# H0FR1.net
KiCad netlist of a schematic drawn in EAGLE
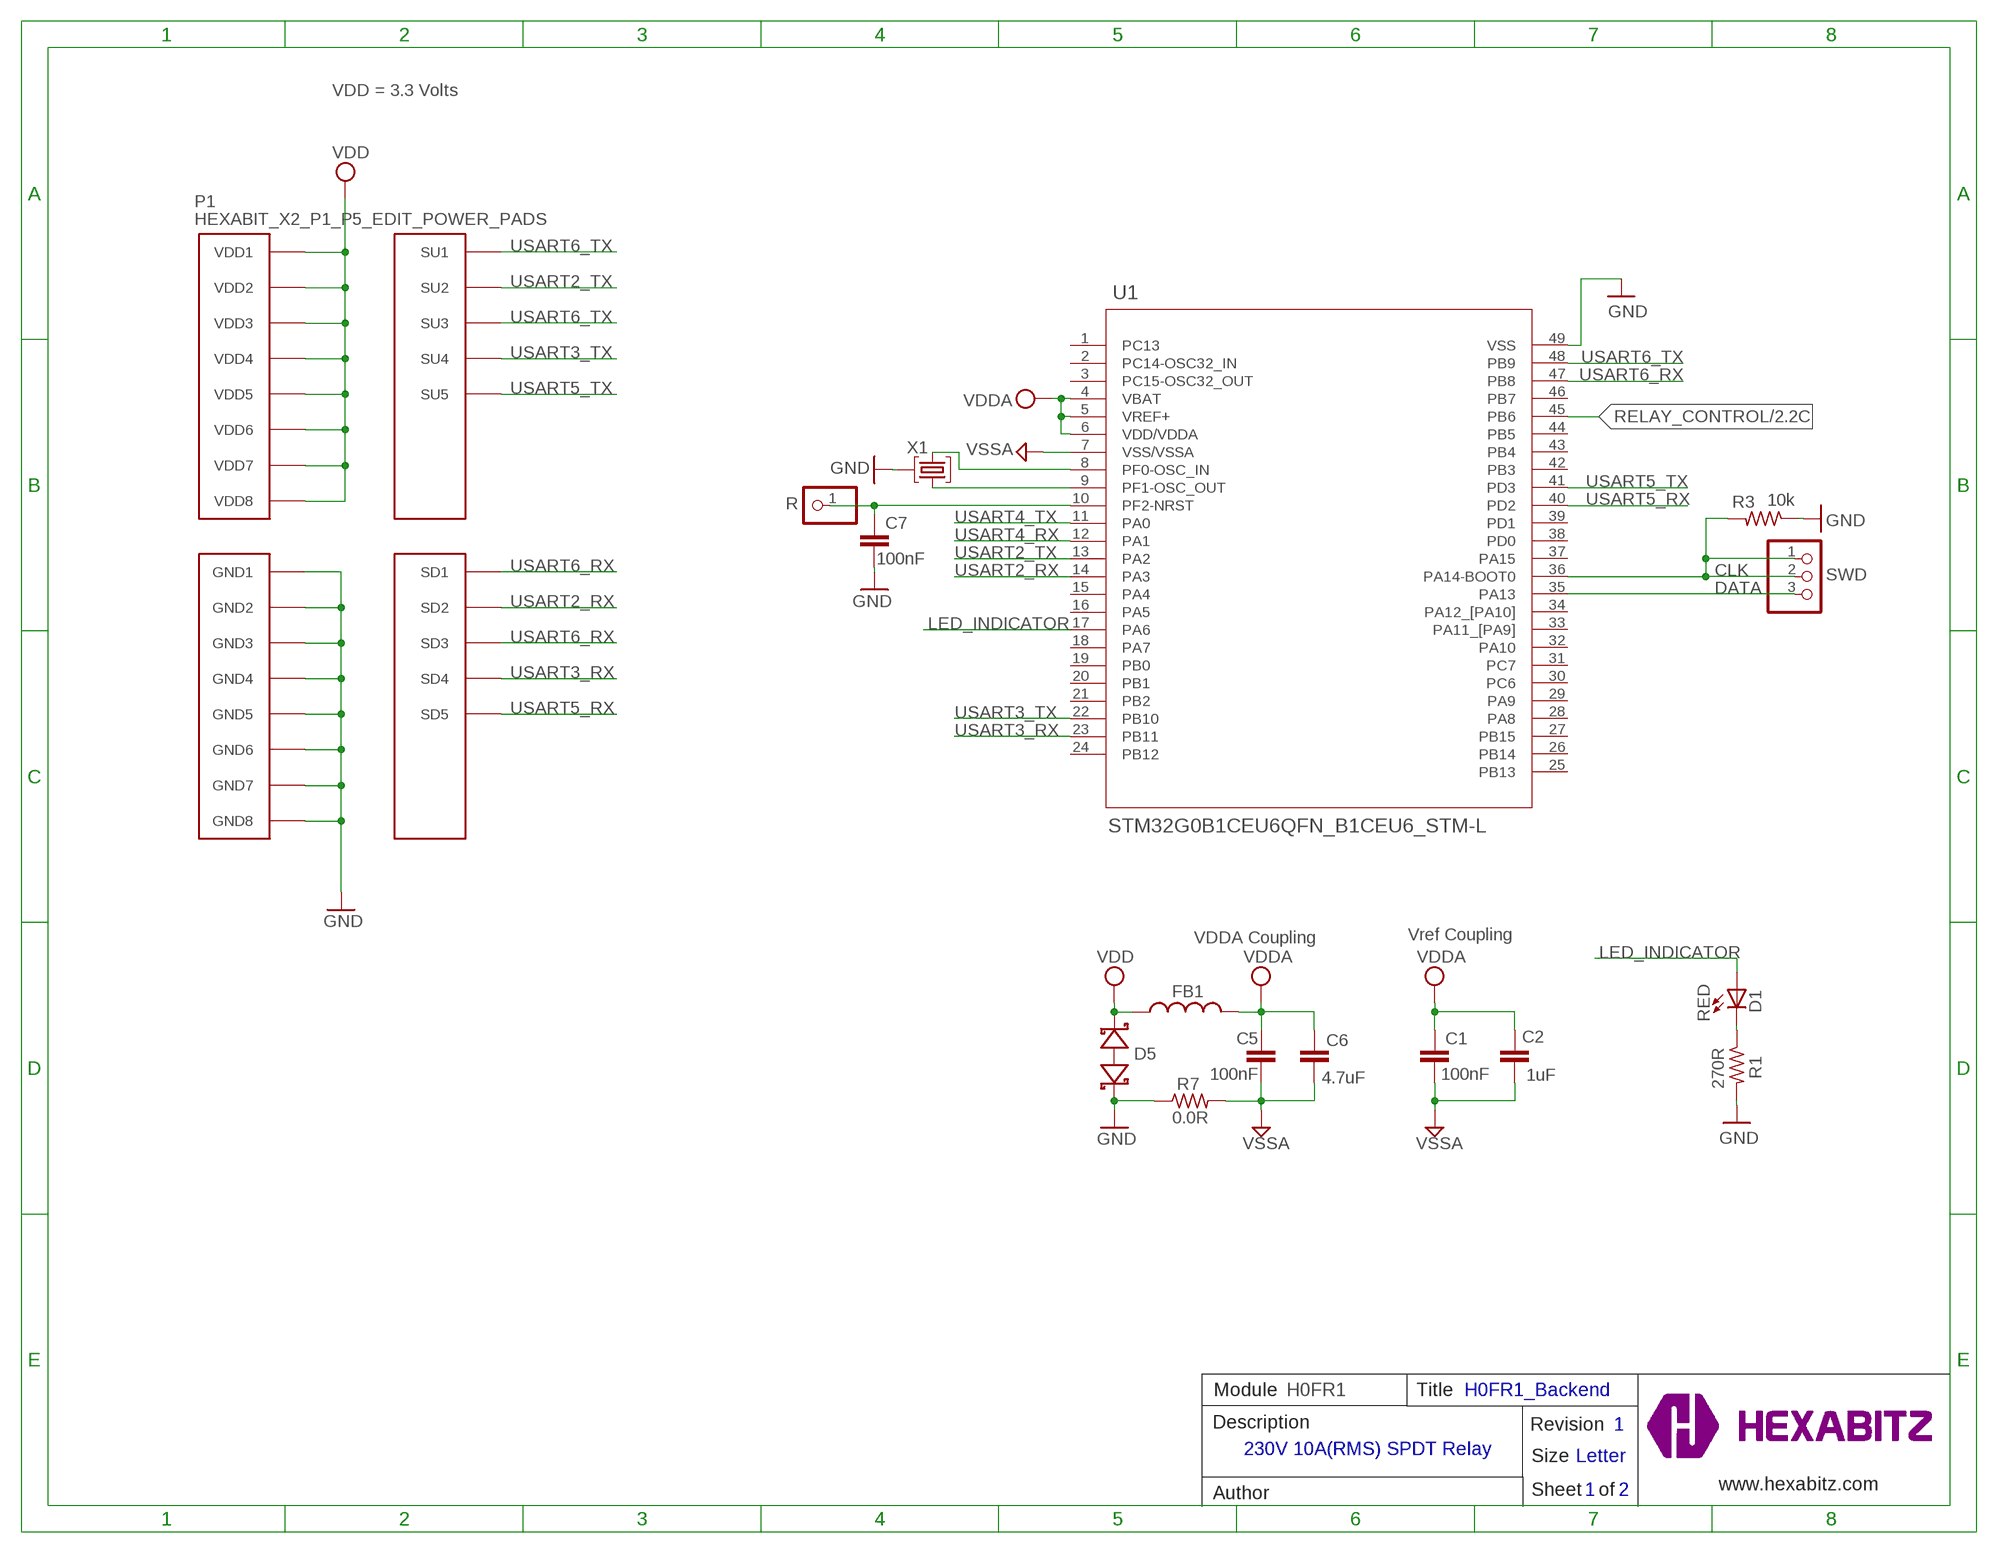
[diagram p0: schematic, sheet 1]
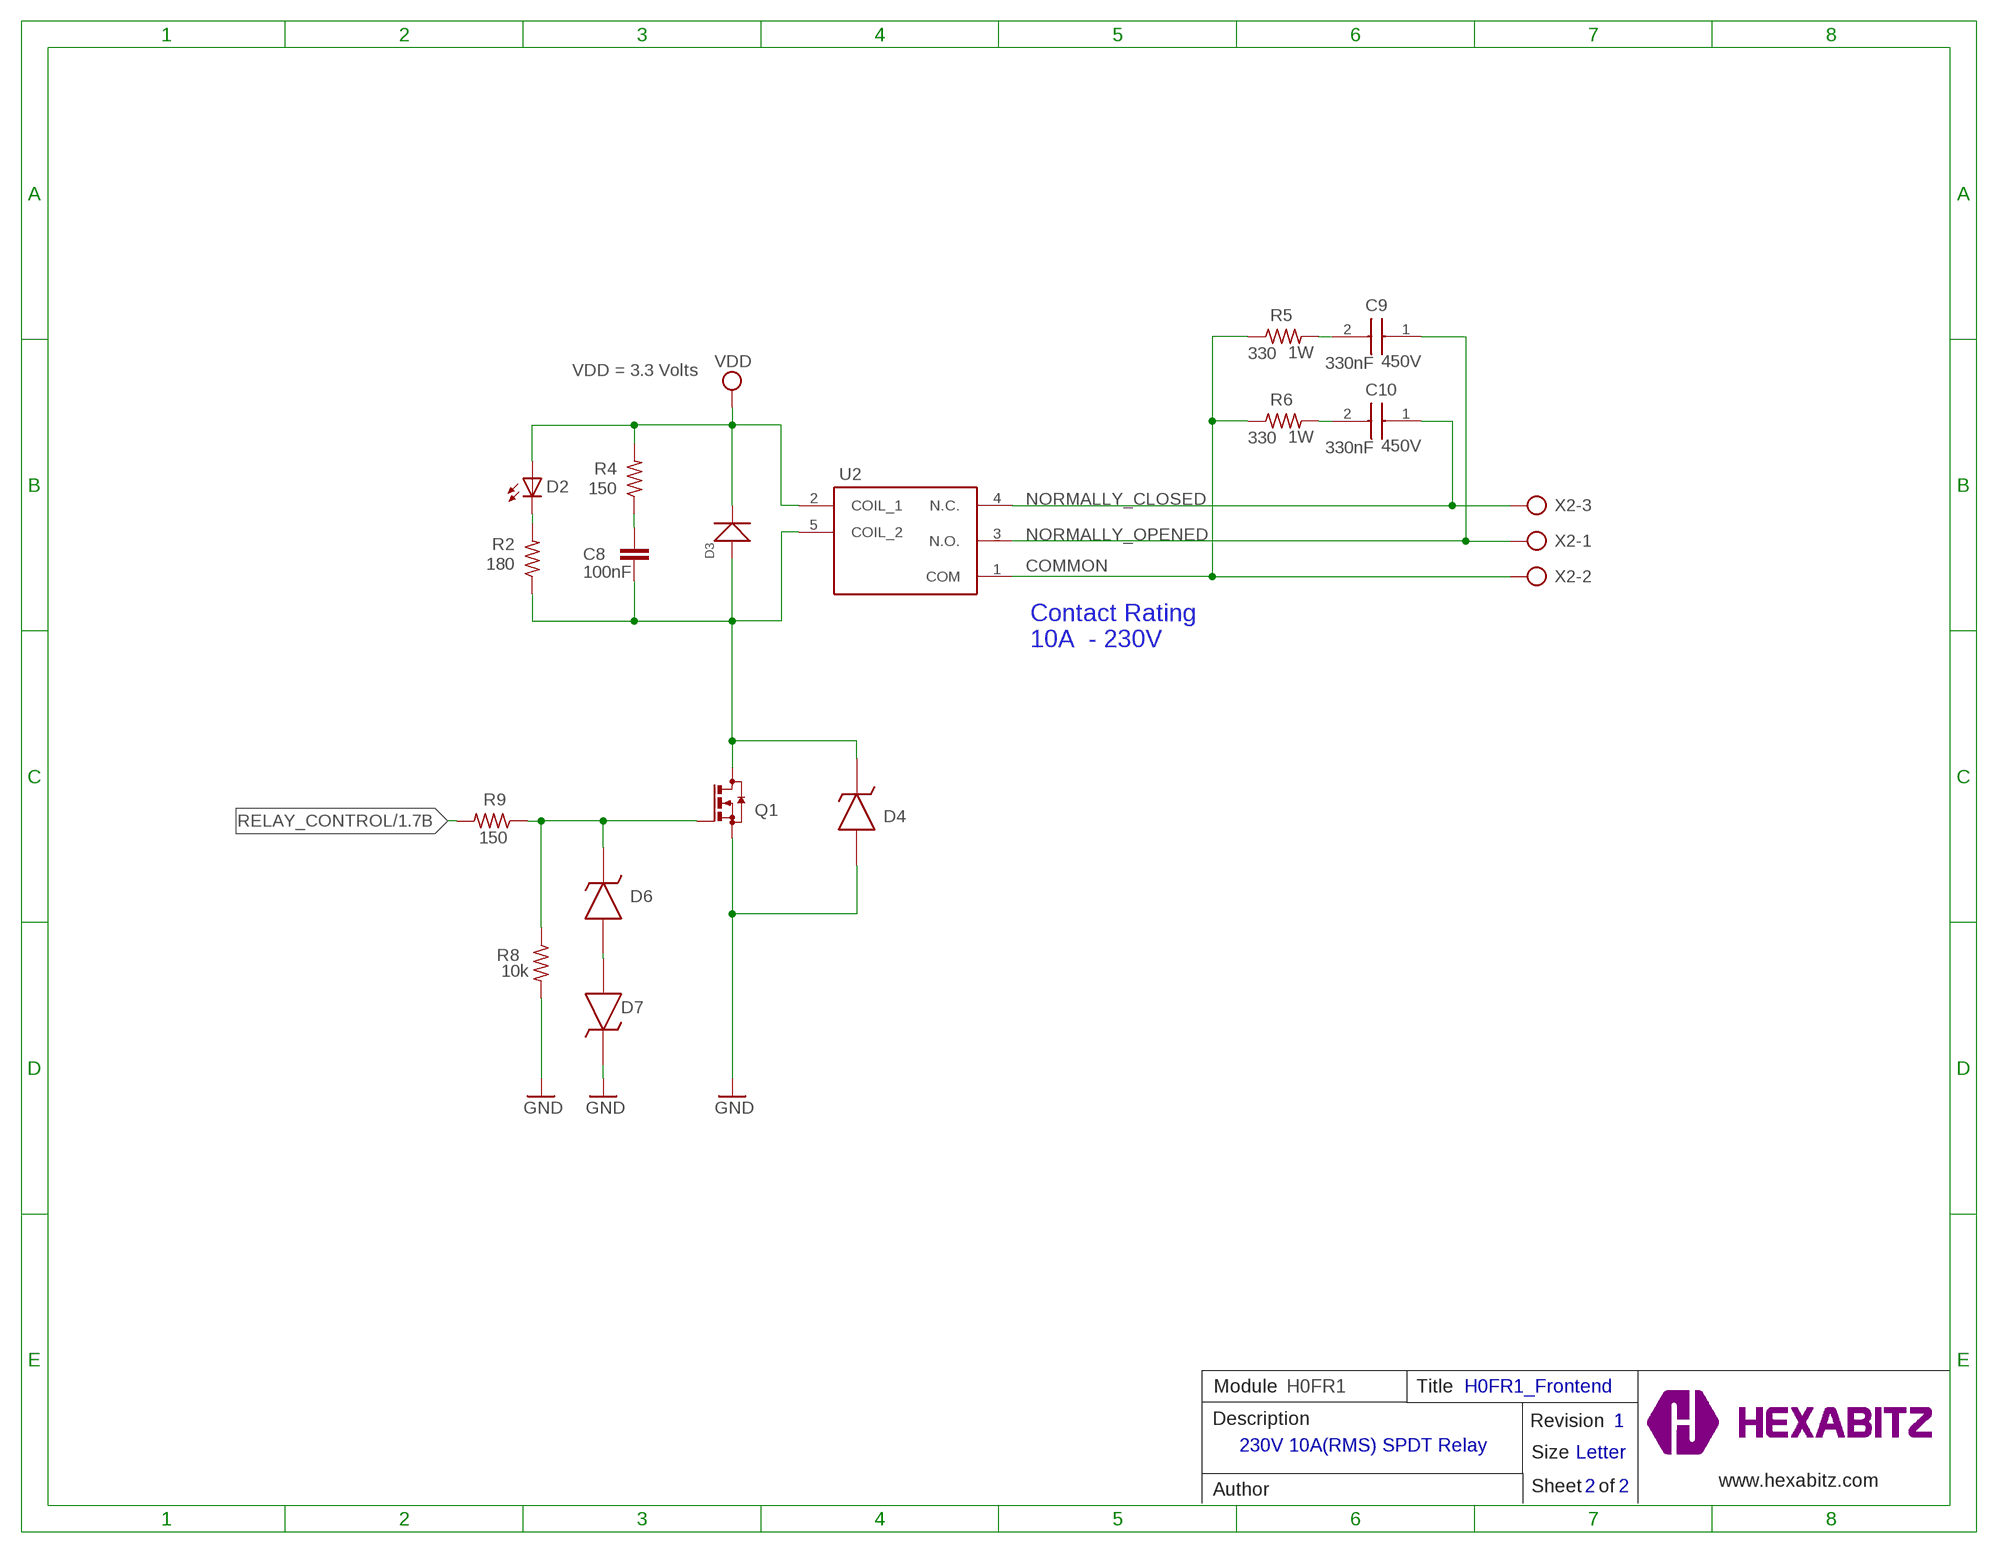
[diagram p1: schematic, sheet 2]

(export (version "E")
  (design (tool "Eeschema 10.0.6"))
  (components
    (comp (ref "C8")
      (value "100nF")
      (footprint "eagle-import:C-0603")
      (fields
        (field (name "CAPACITANCE") "100nF")
        (field (name "MFN") "KEMET")
        (field (name "MPN") "C0603C104K8RACTU")
        (field (name "OCTOPART_URL") "https://octopart.com/c0603c104k8ractu-kemet-145075?r=sp&s=9bS9ASSwSEqMCE9KBEQZ0g")
        (field (name "TOLERANCE") "10%")
        (field (name "VOLTAGE_RATING") "10V")
      )
      (libsource (lib "eagle-import") (part "C-0603"))
    )
    (comp (ref "C9")
      (value "330nF")
      (footprint "eagle-import:B32922Q_(18_X_8.5)")
      (fields
        (field (name "MANUFACTURER_PART_NUMBER") "B32922Q3334K000")
        (field (name "MOUSER_PART_NUMBER") "871-B32922Q3334K000")
        (field (name "VOLTAAGE") "450V")
      )
      (libsource (lib "eagle-import") (part "B32922Q3334K000"))
    )
    (comp (ref "C10")
      (value "330nF")
      (footprint "eagle-import:B32922Q_(18_X_8.5)")
      (fields
        (field (name "MANUFACTURER_PART_NUMBER") "B32922Q3334K000")
        (field (name "MOUSER_PART_NUMBER") "871-B32922Q3334K000")
        (field (name "VOLTAAGE") "450V")
      )
      (libsource (lib "eagle-import") (part "B32922Q3334K000"))
    )
    (comp (ref "D2")
      (value "RED")
      (footprint "eagle-import:VLMS1300-GS08")
      (fields
        (field (name "MPN") "VLMS1300-GS08")
        (field (name "MFN") "Vishay ")
        (field (name "MPN_1") "VLMY1300-GS08")
        (field (name "OCTOPART_URL") "https://octopart.com/vlmy1300-gs08-vishay-21709204")
      )
      (libsource (lib "eagle-import") (part "Hexabitz_VLMS1300-GS08"))
    )
    (comp (ref "D3")
      (value "40V 300MA")
      (footprint "eagle-import:SOD-323")
      (fields (field (name "MPN") "BAT54JFILM"))
      (libsource (lib "eagle-import") (part "BAT54JFILM_SOD-323"))
    )
    (comp (ref "D4")
      (value "MMSZ4705T1GMMSZ4705T1G")
      (footprint "eagle-import:DIO_MMSZ4700T1G")
      (libsource (lib "eagle-import") (part "MMSZ4705T1GMMSZ4705T1G"))
    )
    (comp (ref "D6")
      (value "MMSZ4705T1GMMSZ4705T1G")
      (footprint "eagle-import:DIO_MMSZ4700T1G")
      (libsource (lib "eagle-import") (part "MMSZ4705T1GMMSZ4705T1G"))
    )
    (comp (ref "D7")
      (value "MMSZ4705T1GMMSZ4705T1G")
      (footprint "eagle-import:DIO_MMSZ4700T1G")
      (libsource (lib "eagle-import") (part "MMSZ4705T1GMMSZ4705T1G"))
    )
    (comp (ref "Q1")
      (value "BSS123")
      (footprint "eagle-import:SOT23")
      (libsource (lib "eagle-import") (part "BSS123"))
    )
    (comp (ref "R2")
      (value "180")
      (footprint "eagle-import:R-0603")
      (fields
        (field (name "MFN") "Panasonic")
        (field (name "MPN") "ERJ-3GEYJ181V")
        (field (name "OCTOPART_URL") "https://octopart.com/erj-3geyj181v-panasonic-55403673")
        (field (name "RESISTANCE") "180.0 Ω")
        (field (name "TOLERANCE") "±5%")
      )
      (libsource (lib "eagle-import") (part "R-0603"))
    )
    (comp (ref "R4")
      (value "150")
      (footprint "eagle-import:R-0603")
      (fields
        (field (name "MFN") "Yageo")
        (field (name "MPN") "RC0603JR-07680KL")
        (field (name "OCTOPART_URL") "https://octopart.com/rc0603jr-07680kl-yageo-40953169?r=sp")
        (field (name "RESISTANCE") "680K Ohm")
        (field (name "TOLERANCE") "5%")
      )
      (libsource (lib "eagle-import") (part "R-0603"))
    )
    (comp (ref "R5")
      (value "330")
      (footprint "eagle-import:R2512")
      (fields (field (name "MPN") "RMCF2512JT330R") (field (name "POWER") "1W"))
      (libsource (lib "eagle-import") (part "R-US_R2512"))
    )
    (comp (ref "R6")
      (value "330")
      (footprint "eagle-import:R2512")
      (fields (field (name "MPN") "RMCF2512JT330R") (field (name "POWER") "1W"))
      (libsource (lib "eagle-import") (part "R-US_R2512"))
    )
    (comp (ref "R8")
      (value "10k")
      (footprint "eagle-import:R-0603")
      (fields
        (field (name "MFN") "Yageo")
        (field (name "MPN") "RC0603JR-07680KL")
        (field (name "OCTOPART_URL") "https://octopart.com/rc0603jr-07680kl-yageo-40953169?r=sp")
        (field (name "RESISTANCE") "680K Ohm")
        (field (name "TOLERANCE") "5%")
      )
      (libsource (lib "eagle-import") (part "R-0603"))
    )
    (comp (ref "R9")
      (value "150")
      (footprint "eagle-import:R-0603")
      (fields
        (field (name "MFN") "Yageo")
        (field (name "MPN") "RC0603JR-07680KL")
        (field (name "OCTOPART_URL") "https://octopart.com/rc0603jr-07680kl-yageo-40953169?r=sp")
        (field (name "RESISTANCE") "680K Ohm")
        (field (name "TOLERANCE") "5%")
      )
      (libsource (lib "eagle-import") (part "R-0603"))
    )
    (comp (ref "U2")
      (value "G5LE-14_DC3")
      (footprint "eagle-import:G5LE-14_SPDT")
      (fields
        (field (name "MANUFACTURER_PART_NUMBER") "G5LE-14 DC3")
        (field (name "MOUSER_PART_NUMBER") "653-G5LE-14DC3")
      )
      (libsource (lib "eagle-import") (part "G5LE-14_DC3"))
    )
    (comp (ref "X2")
      (value "AK300/3")
      (footprint "eagle-import:AK300_3")
      (libsource (lib "eagle-import") (part "AK300/3"))
    )
    (comp (ref "C1")
      (value "100nF")
      (footprint "eagle-import:C-0603")
      (fields
        (field (name "CAPACITANCE") "100nF")
        (field (name "MFN") "KEMET")
        (field (name "MPN") "C0603C104K8RACTU")
        (field (name "OCTOPART_URL") "https://octopart.com/c0603c104k8ractu-kemet-145075?r=sp&s=9bS9ASSwSEqMCE9KBEQZ0g")
        (field (name "TOLERANCE") "10%")
        (field (name "VOLTAGE_RATING") "10V")
      )
      (libsource (lib "eagle-import") (part "C-0603"))
    )
    (comp (ref "C2")
      (value "1uF")
      (footprint "eagle-import:C-0805")
      (fields
        (field (name "CAPACITANCE") "1.00uF")
        (field (name "MFN") "Yageo")
        (field (name "MPN") "CC0805KKX7R7BB105")
        (field (name "OCTOPART_URL") "https://octopart.com/cc0805kkx7r7bb105-yageo-8376555?r=sp&s=YKl1wwtkROau_X5nniH2ig")
        (field (name "TOLERANCE") "10%")
        (field (name "VOLTAGE_RATING") "16V")
      )
      (libsource (lib "eagle-import") (part "C-0805"))
    )
    (comp (ref "C5")
      (value "100nF")
      (footprint "eagle-import:C-0603")
      (libsource (lib "eagle-import") (part "C-0603"))
    )
    (comp (ref "C6")
      (value "4.7uF")
      (footprint "eagle-import:C-0805")
      (fields
        (field (name "CAPACITANCE") "4.7uF")
        (field (name "MFN") "Murata")
        (field (name "MPN") "GRM21BC81E475KA12L")
        (field (name "OCTOPART_URL") "https://octopart.com/grm21bc81e475ka12l-murata-10331911?r=sp&s=RY3qZSD8T6mG6TC9CHI5qQ")
        (field (name "TOLERANCE") "10%")
        (field (name "VOLTAGE_RATING") "25V")
      )
      (libsource (lib "eagle-import") (part "C-0805"))
    )
    (comp (ref "C7")
      (value "100nF")
      (footprint "eagle-import:C-0603")
      (libsource (lib "eagle-import") (part "C-0603"))
    )
    (comp (ref "D1")
      (value "RED")
      (footprint "eagle-import:VLMS1300-GS08")
      (fields
        (field (name "MPN") "VLMS1300-GS08")
        (field (name "MFN") "Vishay")
        (field (name "MPN_1") "VLMS1300-GS08")
        (field (name "OCTOPART_URL") "https://octopart.com/vlms1300-gs08-vishay-21709201?r=sp&s=_gcP4_q8T1SC6PJQPTQ9yA")
      )
      (libsource (lib "eagle-import") (part "VLMS1300-GS08"))
    )
    (comp (ref "D5")
      (value "BOURNS_CDSOD323-T03SCBOURNS_CDSOD323-T03SC_0_0")
      (footprint "eagle-import:BOURNS_CDSOD323-T03SC_0")
      (fields (field (name "MPN") "CDSOD323-T03SC"))
      (libsource (lib "eagle-import") (part "BOURNS_CDSOD323-T03SCBOURNS_CDSOD323-T03SC_0_0"))
    )
    (comp (ref "FB1")
      (value "FB-0603")
      (footprint "eagle-import:FB-0603")
      (libsource (lib "eagle-import") (part "FB-0603"))
    )
    (comp (ref "P1")
      (value "HEXABIT_X2_P1_P5_EDIT_POWER_PADS")
      (footprint "eagle-import:HEXABIT_X2_P1_P5_EDIT_POWER_PADS")
      (libsource (lib "eagle-import") (part "HEXABIT_X2_P1_P5_EDIT_POWER_PADS"))
    )
    (comp (ref "R")
      (value "R")
      (footprint "eagle-import:1X01")
      (fields (field (name "MPN") "87227-1"))
      (libsource (lib "eagle-import") (part "PINHD-1X1"))
    )
    (comp (ref "R1")
      (value "270R")
      (footprint "eagle-import:R-0603")
      (libsource (lib "eagle-import") (part "R-0603"))
    )
    (comp (ref "R3")
      (value "10k")
      (footprint "eagle-import:R-0603")
      (fields
        (field (name "MFN") "Yageo")
        (field (name "MPN") "RC0603JR-0710KL")
        (field (name "OCTOPART_URL") "https://octopart.com/search?q=RC0603JR-0710KL&start=0")
        (field (name "RESISTANCE") "10.0K Ohm")
        (field (name "TOLERANCE") "5%")
      )
      (libsource (lib "eagle-import") (part "R-0603"))
    )
    (comp (ref "R7")
      (value "0.0R")
      (footprint "eagle-import:R-0603")
      (libsource (lib "eagle-import") (part "R-0603"))
    )
    (comp (ref "SWD")
      (value "PINHD-1X3SWD")
      (footprint "eagle-import:SWD")
      (libsource (lib "eagle-import") (part "PINHD-1X3SWD"))
    )
    (comp (ref "TRIMBLE-LOGO2")
      (value "HEXA-LOGO")
      (footprint "eagle-import:HEXA-LOGO")
      (libsource (lib "eagle-import") (part "HEXA-LOGO"))
    )
    (comp (ref "U1")
      (value "STM32G0B1CEU6QFN_B1CEU6_STM-L")
      (footprint "eagle-import:QFN_B1CEU6_STM-L")
      (fields
        (field (name "MANUFACTURER_PART_NUMBER") "STM32G0B1CEU6")
        (field (name "COPYRIGHT") "Copyright (C) 2021 Ultra Librarian. All rights reserved.")
      )
      (libsource (lib "eagle-import") (part "STM32G0B1CEU6QFN_B1CEU6_STM-L"))
    )
    (comp (ref "X1")
      (value "XTALL_CSTCE8M00G52")
      (footprint "eagle-import:XTALL_CSTCE8M00G52")
      (fields (field (name "MPN") "CSTCE8M00G52Z-R0"))
      (libsource (lib "eagle-import") (part "XTALL_CSTCE8M00G52"))
    )
  )
  (nets
    (net (code "1") (name "CLK") (class "Default")
      (node (ref "R3") (pin "2") (pinfunction "2_2") (pintype "passive"))
      (node (ref "SWD") (pin "1") (pinfunction "1_1") (pintype "passive"))
      (node (ref "SWD") (pin "2") (pinfunction "2_2") (pintype "passive"))
      (node (ref "U1") (pin "36") (pinfunction "PA14-BOOT0_36") (pintype "bidirectional"))
    )
    (net (code "2") (name "COMMON") (class "Default")
      (node (ref "R5") (pin "1") (pinfunction "1_1") (pintype "passive"))
      (node (ref "R6") (pin "1") (pinfunction "1_1") (pintype "passive"))
      (node (ref "U2") (pin "1") (pinfunction "COM_1") (pintype "bidirectional"))
      (node (ref "X2") (pin "2") (pinfunction "KL_2") (pintype "passive"))
    )
    (net (code "3") (name "DATA") (class "Default")
      (node (ref "SWD") (pin "3") (pinfunction "3_3") (pintype "passive"))
      (node (ref "U1") (pin "35") (pinfunction "PA13_35") (pintype "bidirectional"))
    )
    (net (code "4") (name "GND") (class "Default")
      (node (ref "C7") (pin "2") (pinfunction "2_2") (pintype "passive"))
      (node (ref "D4") (pin "A") (pinfunction "A_A") (pintype "bidirectional"))
      (node (ref "D5") (pin "2") (pinfunction "C_2") (pintype "passive"))
      (node (ref "D7") (pin "K") (pinfunction "K_K") (pintype "bidirectional"))
      (node (ref "P1") (pin "PAD_PD11") (pinfunction "GND1_PAD_PD11") (pintype "power_in"))
      (node (ref "P1") (pin "PAD_PD12") (pinfunction "GND2_PAD_PD12") (pintype "power_in"))
      (node (ref "P1") (pin "PAD_PD13") (pinfunction "GND3_PAD_PD13") (pintype "power_in"))
      (node (ref "P1") (pin "PAD_PD14") (pinfunction "GND4_PAD_PD14") (pintype "power_in"))
      (node (ref "P1") (pin "PAD_PD17") (pinfunction "GND5_PAD_PD17") (pintype "power_in"))
      (node (ref "P1") (pin "PAD_PD18") (pinfunction "GND6_PAD_PD18") (pintype "power_in"))
      (node (ref "P1") (pin "PAD_PD19") (pinfunction "GND7_PAD_PD19") (pintype "power_in"))
      (node (ref "P1") (pin "PAD_PD20") (pinfunction "GND8_PAD_PD20") (pintype "power_in"))
      (node (ref "Q1") (pin "2") (pinfunction "S_2") (pintype "passive"))
      (node (ref "R1") (pin "2") (pinfunction "2_2") (pintype "passive"))
      (node (ref "R3") (pin "1") (pinfunction "1_1") (pintype "passive"))
      (node (ref "R7") (pin "1") (pinfunction "1_1") (pintype "passive"))
      (node (ref "R8") (pin "2") (pinfunction "2_2") (pintype "passive"))
      (node (ref "U1") (pin "49") (pinfunction "VSS_49") (pintype "passive"))
      (node (ref "X1") (pin "P$2") (pinfunction "2_P$2") (pintype "passive"))
    )
    (net (code "5") (name "LED_INDICATOR") (class "Default")
      (node (ref "D1") (pin "A") (pinfunction "A_A") (pintype "passive"))
      (node (ref "U1") (pin "17") (pinfunction "PA6_17") (pintype "bidirectional"))
    )
    (net (code "6") (name "NORMALLY_CLOSED") (class "Default")
      (node (ref "C10") (pin "1") (pinfunction "1_1") (pintype "bidirectional"))
      (node (ref "U2") (pin "4") (pinfunction "N.C._4") (pintype "bidirectional"))
      (node (ref "X2") (pin "3") (pinfunction "KL_3") (pintype "passive"))
    )
    (net (code "7") (name "NORMALLY_OPENED") (class "Default")
      (node (ref "C9") (pin "1") (pinfunction "1_1") (pintype "bidirectional"))
      (node (ref "U2") (pin "3") (pinfunction "N.O._3") (pintype "bidirectional"))
      (node (ref "X2") (pin "1") (pinfunction "KL_1") (pintype "passive"))
    )
    (net (code "8") (name "Net-(C8-Pad1)") (class "Default")
      (node (ref "C8") (pin "1") (pinfunction "1_1") (pintype "passive"))
      (node (ref "R4") (pin "1") (pinfunction "1_1") (pintype "passive"))
    )
    (net (code "9") (name "Net-(C9-Pad2)") (class "Default")
      (node (ref "C9") (pin "2") (pinfunction "2_2") (pintype "bidirectional"))
      (node (ref "R5") (pin "2") (pinfunction "2_2") (pintype "passive"))
    )
    (net (code "10") (name "Net-(C10-Pad2)") (class "Default")
      (node (ref "C10") (pin "2") (pinfunction "2_2") (pintype "bidirectional"))
      (node (ref "R6") (pin "2") (pinfunction "2_2") (pintype "passive"))
    )
    (net (code "11") (name "Net-(D1-PadC)") (class "Default")
      (node (ref "D1") (pin "C") (pinfunction "C_C") (pintype "passive"))
      (node (ref "R1") (pin "1") (pinfunction "1_1") (pintype "passive"))
    )
    (net (code "12") (name "Net-(D2-PadC)") (class "Default")
      (node (ref "D2") (pin "C") (pinfunction "C_C") (pintype "passive"))
      (node (ref "R2") (pin "2") (pinfunction "2_2") (pintype "passive"))
    )
    (net (code "13") (name "Net-(D6-PadA)") (class "Default")
      (node (ref "D6") (pin "A") (pinfunction "A_A") (pintype "bidirectional"))
      (node (ref "D7") (pin "A") (pinfunction "A_A") (pintype "bidirectional"))
    )
    (net (code "14") (name "Net-(Q1-D)") (class "Default")
      (node (ref "C8") (pin "2") (pinfunction "2_2") (pintype "passive"))
      (node (ref "D3") (pin "+") (pinfunction "+_+") (pintype "passive"))
      (node (ref "D4") (pin "K") (pinfunction "K_K") (pintype "bidirectional"))
      (node (ref "Q1") (pin "3") (pinfunction "D_3") (pintype "passive"))
      (node (ref "R2") (pin "1") (pinfunction "1_1") (pintype "passive"))
      (node (ref "U2") (pin "5") (pinfunction "COIL_2_5") (pintype "bidirectional"))
    )
    (net (code "15") (name "Net-(Q1-G)") (class "Default")
      (node (ref "D6") (pin "K") (pinfunction "K_K") (pintype "bidirectional"))
      (node (ref "Q1") (pin "1") (pinfunction "G_1") (pintype "passive"))
      (node (ref "R8") (pin "1") (pinfunction "1_1") (pintype "passive"))
      (node (ref "R9") (pin "1") (pinfunction "1_1") (pintype "passive"))
    )
    (net (code "16") (name "Net-(U1-PF0-OSC_IN)") (class "Default")
      (node (ref "U1") (pin "8") (pinfunction "PF0-OSC_IN_8") (pintype "bidirectional"))
      (node (ref "X1") (pin "P$3") (pinfunction "3_P$3") (pintype "passive"))
    )
    (net (code "17") (name "Net-(U1-PF1-OSC_OUT)") (class "Default")
      (node (ref "U1") (pin "9") (pinfunction "PF1-OSC_OUT_9") (pintype "output"))
      (node (ref "X1") (pin "P$1") (pinfunction "1_P$1") (pintype "passive"))
    )
    (net (code "18") (name "Net-(U1-PF2-NRST)") (class "Default")
      (node (ref "C7") (pin "1") (pinfunction "1_1") (pintype "passive"))
      (node (ref "R") (pin "1") (pinfunction "1_1") (pintype "passive"))
      (node (ref "U1") (pin "10") (pinfunction "PF2-NRST_10") (pintype "bidirectional"))
    )
    (net (code "19") (name "RELAY_CONTROL") (class "Default")
      (node (ref "R9") (pin "2") (pinfunction "2_2") (pintype "passive"))
      (node (ref "U1") (pin "45") (pinfunction "PB6_45") (pintype "bidirectional"))
    )
    (net (code "20") (name "USART2_RX") (class "Default")
      (node (ref "P1") (pin "PAD_PD2") (pinfunction "SD2_PAD_PD2") (pintype "bidirectional"))
      (node (ref "U1") (pin "14") (pinfunction "PA3_14") (pintype "bidirectional"))
    )
    (net (code "21") (name "USART2_TX") (class "Default")
      (node (ref "P1") (pin "PAD_PU2") (pinfunction "SU2_PAD_PU2") (pintype "bidirectional"))
      (node (ref "U1") (pin "13") (pinfunction "PA2_13") (pintype "bidirectional"))
    )
    (net (code "22") (name "USART3_RX") (class "Default")
      (node (ref "P1") (pin "PAD_PD4") (pinfunction "SD4_PAD_PD4") (pintype "bidirectional"))
      (node (ref "U1") (pin "23") (pinfunction "PB11_23") (pintype "bidirectional"))
    )
    (net (code "23") (name "USART3_TX") (class "Default")
      (node (ref "P1") (pin "PAD_PU4") (pinfunction "SU4_PAD_PU4") (pintype "bidirectional"))
      (node (ref "U1") (pin "22") (pinfunction "PB10_22") (pintype "bidirectional"))
    )
    (net (code "24") (name "USART4_RX") (class "Default")
      (node (ref "U1") (pin "12") (pinfunction "PA1_12") (pintype "bidirectional"))
    )
    (net (code "25") (name "USART4_TX") (class "Default")
      (node (ref "U1") (pin "11") (pinfunction "PA0_11") (pintype "bidirectional"))
    )
    (net (code "26") (name "USART5_RX") (class "Default")
      (node (ref "P1") (pin "PAD_PD5") (pinfunction "SD5_PAD_PD5") (pintype "bidirectional"))
      (node (ref "U1") (pin "40") (pinfunction "PD2_40") (pintype "bidirectional"))
    )
    (net (code "27") (name "USART5_TX") (class "Default")
      (node (ref "P1") (pin "PAD_PU5") (pinfunction "SU5_PAD_PU5") (pintype "bidirectional"))
      (node (ref "U1") (pin "41") (pinfunction "PD3_41") (pintype "bidirectional"))
    )
    (net (code "28") (name "USART6_RX") (class "Default")
      (node (ref "P1") (pin "PAD_PD1") (pinfunction "SD1_PAD_PD1") (pintype "bidirectional"))
      (node (ref "P1") (pin "PAD_PD3") (pinfunction "SD3_PAD_PD3") (pintype "bidirectional"))
      (node (ref "U1") (pin "47") (pinfunction "PB8_47") (pintype "bidirectional"))
    )
    (net (code "29") (name "USART6_TX") (class "Default")
      (node (ref "P1") (pin "PAD_PU1") (pinfunction "SU1_PAD_PU1") (pintype "bidirectional"))
      (node (ref "P1") (pin "PAD_PU3") (pinfunction "SU3_PAD_PU3") (pintype "bidirectional"))
      (node (ref "U1") (pin "48") (pinfunction "PB9_48") (pintype "bidirectional"))
    )
    (net (code "30") (name "VDD") (class "Default")
      (node (ref "D2") (pin "A") (pinfunction "A_A") (pintype "passive"))
      (node (ref "D3") (pin "-") (pinfunction "-_-") (pintype "passive"))
      (node (ref "D5") (pin "1") (pinfunction "A_1") (pintype "passive"))
      (node (ref "FB1") (pin "1") (pinfunction "1_1") (pintype "passive"))
      (node (ref "P1") (pin "PAD_PU11") (pinfunction "VDD1_PAD_PU11") (pintype "power_in"))
      (node (ref "P1") (pin "PAD_PU12") (pinfunction "VDD2_PAD_PU12") (pintype "power_in"))
      (node (ref "P1") (pin "PAD_PU13") (pinfunction "VDD3_PAD_PU13") (pintype "power_in"))
      (node (ref "P1") (pin "PAD_PU14") (pinfunction "VDD4_PAD_PU14") (pintype "power_in"))
      (node (ref "P1") (pin "PAD_PU17") (pinfunction "VDD5_PAD_PU17") (pintype "power_in"))
      (node (ref "P1") (pin "PAD_PU18") (pinfunction "VDD6_PAD_PU18") (pintype "power_in"))
      (node (ref "P1") (pin "PAD_PU19") (pinfunction "VDD7_PAD_PU19") (pintype "power_in"))
      (node (ref "P1") (pin "PAD_PU20") (pinfunction "VDD8_PAD_PU20") (pintype "power_in"))
      (node (ref "R4") (pin "2") (pinfunction "2_2") (pintype "passive"))
      (node (ref "U2") (pin "2") (pinfunction "COIL_1_2") (pintype "bidirectional"))
    )
    (net (code "31") (name "VDDA") (class "Default")
      (node (ref "C1") (pin "1") (pinfunction "1_1") (pintype "passive"))
      (node (ref "C2") (pin "1") (pinfunction "1_1") (pintype "passive"))
      (node (ref "C5") (pin "1") (pinfunction "1_1") (pintype "passive"))
      (node (ref "C6") (pin "1") (pinfunction "1_1") (pintype "passive"))
      (node (ref "FB1") (pin "2") (pinfunction "2_2") (pintype "passive"))
      (node (ref "U1") (pin "4") (pinfunction "VBAT_4") (pintype "passive"))
      (node (ref "U1") (pin "5") (pinfunction "VREF+_5") (pintype "power_in"))
      (node (ref "U1") (pin "6") (pinfunction "VDD/VDDA_6") (pintype "power_in"))
    )
    (net (code "32") (name "VSSA") (class "Default")
      (node (ref "C1") (pin "2") (pinfunction "2_2") (pintype "passive"))
      (node (ref "C2") (pin "2") (pinfunction "2_2") (pintype "passive"))
      (node (ref "C5") (pin "2") (pinfunction "2_2") (pintype "passive"))
      (node (ref "C6") (pin "2") (pinfunction "2_2") (pintype "passive"))
      (node (ref "R7") (pin "2") (pinfunction "2_2") (pintype "passive"))
      (node (ref "U1") (pin "7") (pinfunction "VSS/VSSA_7") (pintype "passive"))
    )
    (net (code "33") (name "unconnected-(U1-PA4-Pad15)") (class "Default")
      (node (ref "U1") (pin "15") (pinfunction "PA4_15") (pintype "bidirectional"))
    )
    (net (code "34") (name "unconnected-(U1-PA5-Pad16)") (class "Default")
      (node (ref "U1") (pin "16") (pinfunction "PA5_16") (pintype "bidirectional"))
    )
    (net (code "35") (name "unconnected-(U1-PA7-Pad18)") (class "Default")
      (node (ref "U1") (pin "18") (pinfunction "PA7_18") (pintype "bidirectional"))
    )
    (net (code "36") (name "unconnected-(U1-PA8-Pad28)") (class "Default")
      (node (ref "U1") (pin "28") (pinfunction "PA8_28") (pintype "bidirectional"))
    )
    (net (code "37") (name "unconnected-(U1-PA9-Pad29)") (class "Default")
      (node (ref "U1") (pin "29") (pinfunction "PA9_29") (pintype "bidirectional"))
    )
    (net (code "38") (name "unconnected-(U1-PA10-Pad32)") (class "Default")
      (node (ref "U1") (pin "32") (pinfunction "PA10_32") (pintype "bidirectional"))
    )
    (net (code "39") (name "unconnected-(U1-PA11_[PA9]-Pad33)") (class "Default")
      (node (ref "U1") (pin "33") (pinfunction "PA11_[PA9]_33") (pintype "bidirectional"))
    )
    (net (code "40") (name "unconnected-(U1-PA12_[PA10]-Pad34)") (class "Default")
      (node (ref "U1") (pin "34") (pinfunction "PA12_[PA10]_34") (pintype "bidirectional"))
    )
    (net (code "41") (name "unconnected-(U1-PA15-Pad37)") (class "Default")
      (node (ref "U1") (pin "37") (pinfunction "PA15_37") (pintype "bidirectional"))
    )
    (net (code "42") (name "unconnected-(U1-PB0-Pad19)") (class "Default")
      (node (ref "U1") (pin "19") (pinfunction "PB0_19") (pintype "bidirectional"))
    )
    (net (code "43") (name "unconnected-(U1-PB1-Pad20)") (class "Default")
      (node (ref "U1") (pin "20") (pinfunction "PB1_20") (pintype "bidirectional"))
    )
    (net (code "44") (name "unconnected-(U1-PB2-Pad21)") (class "Default")
      (node (ref "U1") (pin "21") (pinfunction "PB2_21") (pintype "bidirectional"))
    )
    (net (code "45") (name "unconnected-(U1-PB3-Pad42)") (class "Default")
      (node (ref "U1") (pin "42") (pinfunction "PB3_42") (pintype "bidirectional"))
    )
    (net (code "46") (name "unconnected-(U1-PB4-Pad43)") (class "Default")
      (node (ref "U1") (pin "43") (pinfunction "PB4_43") (pintype "bidirectional"))
    )
    (net (code "47") (name "unconnected-(U1-PB5-Pad44)") (class "Default")
      (node (ref "U1") (pin "44") (pinfunction "PB5_44") (pintype "bidirectional"))
    )
    (net (code "48") (name "unconnected-(U1-PB7-Pad46)") (class "Default")
      (node (ref "U1") (pin "46") (pinfunction "PB7_46") (pintype "bidirectional"))
    )
    (net (code "49") (name "unconnected-(U1-PB12-Pad24)") (class "Default")
      (node (ref "U1") (pin "24") (pinfunction "PB12_24") (pintype "bidirectional"))
    )
    (net (code "50") (name "unconnected-(U1-PB13-Pad25)") (class "Default")
      (node (ref "U1") (pin "25") (pinfunction "PB13_25") (pintype "bidirectional"))
    )
    (net (code "51") (name "unconnected-(U1-PB14-Pad26)") (class "Default")
      (node (ref "U1") (pin "26") (pinfunction "PB14_26") (pintype "bidirectional"))
    )
    (net (code "52") (name "unconnected-(U1-PB15-Pad27)") (class "Default")
      (node (ref "U1") (pin "27") (pinfunction "PB15_27") (pintype "bidirectional"))
    )
    (net (code "53") (name "unconnected-(U1-PC6-Pad30)") (class "Default")
      (node (ref "U1") (pin "30") (pinfunction "PC6_30") (pintype "bidirectional"))
    )
    (net (code "54") (name "unconnected-(U1-PC7-Pad31)") (class "Default")
      (node (ref "U1") (pin "31") (pinfunction "PC7_31") (pintype "bidirectional"))
    )
    (net (code "55") (name "unconnected-(U1-PC13-Pad1)") (class "Default")
      (node (ref "U1") (pin "1") (pinfunction "PC13_1") (pintype "bidirectional"))
    )
    (net (code "56") (name "unconnected-(U1-PC14-OSC32_IN-Pad2)") (class "Default")
      (node (ref "U1") (pin "2") (pinfunction "PC14-OSC32_IN_2") (pintype "bidirectional"))
    )
    (net (code "57") (name "unconnected-(U1-PC15-OSC32_OUT-Pad3)") (class "Default")
      (node (ref "U1") (pin "3") (pinfunction "PC15-OSC32_OUT_3") (pintype "output"))
    )
    (net (code "58") (name "unconnected-(U1-PD0-Pad38)") (class "Default")
      (node (ref "U1") (pin "38") (pinfunction "PD0_38") (pintype "bidirectional"))
    )
    (net (code "59") (name "unconnected-(U1-PD1-Pad39)") (class "Default")
      (node (ref "U1") (pin "39") (pinfunction "PD1_39") (pintype "bidirectional"))
    )
  )
)
